# linearInjector_main.net
KiCad netlist of a schematic drawn in Altium Designer
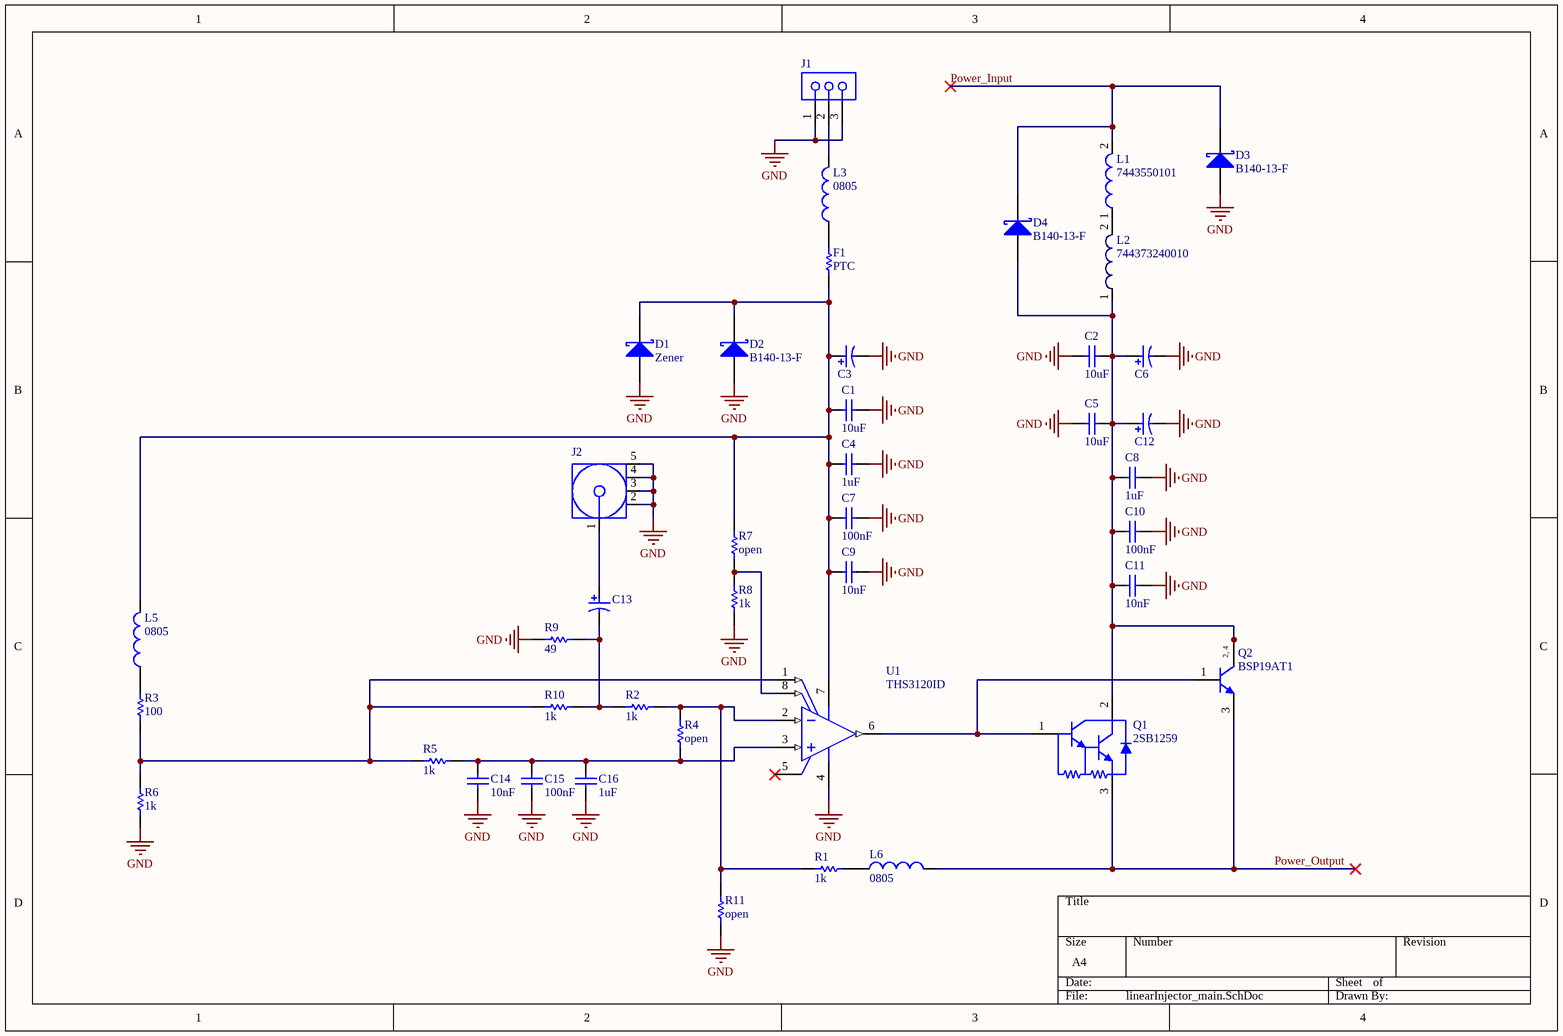
[diagram p0: linearInjector_main.SchDoc]

(export (version "E")
  (design (tool "Eeschema 10.0.6"))
  (components
    (comp (ref "C1")
      (value "10uF")
      (footprint "CAPC1206(3216)130_M")
      (fields (field (name "TOLERANCE") "-20% to +80%"))
      (libsource (lib "Altium Content Vault") (part "CAP"))
    )
    (comp (ref "C2")
      (value "10uF")
      (footprint "CAPC1206(3216)130_L")
      (fields (field (name "TOLERANCE") "-20% to +80%"))
      (libsource (lib "Altium Content Vault") (part "CAP"))
    )
    (comp (ref "C3")
      (value "alum")
      (footprint "PNSC-NF-A_V")
      (description "5mm lead pitch")
      (fields (field (name "VOLTAGE") "5.5Vdc") (field (name "TOLERANCE") "-20→+80%"))
      (libsource (lib "Altium Content Vault") (part "CAP-P-2"))
    )
    (comp (ref "C4")
      (value "1uF")
      (footprint "CAPC0805(2012)75_M")
      (fields (field (name "TOLERANCE") "-20% to +80%"))
      (libsource (lib "Altium Content Vault") (part "CAP"))
    )
    (comp (ref "C5")
      (value "10uF")
      (footprint "CAPC1206(3216)130_L")
      (fields (field (name "TOLERANCE") "-20% to +80%"))
      (libsource (lib "Altium Content Vault") (part "CAP"))
    )
    (comp (ref "C6")
      (value "alum")
      (footprint "PNSC-NF-A_V")
      (description "5mm lead pitch")
      (fields (field (name "VOLTAGE") "5.5Vdc") (field (name "TOLERANCE") "-20→+80%"))
      (libsource (lib "Altium Content Vault") (part "CAP-P-2"))
    )
    (comp (ref "C7")
      (value "100nF")
      (footprint "CAPC0805(2012)75_M")
      (fields (field (name "TOLERANCE") "-20% to +80%"))
      (libsource (lib "Altium Content Vault") (part "CAP"))
    )
    (comp (ref "C8")
      (value "1uF")
      (footprint "CAPC0805(2012)75_M")
      (fields (field (name "TOLERANCE") "-20% to +80%"))
      (libsource (lib "Altium Content Vault") (part "CAP"))
    )
    (comp (ref "C9")
      (value "10nF")
      (footprint "CAPC0805(2012)75_M")
      (fields (field (name "TOLERANCE") "-20% to +80%"))
      (libsource (lib "Altium Content Vault") (part "CAP"))
    )
    (comp (ref "C10")
      (value "100nF")
      (footprint "CAPC0805(2012)75_M")
      (fields (field (name "TOLERANCE") "-20% to +80%"))
      (libsource (lib "Altium Content Vault") (part "CAP"))
    )
    (comp (ref "C11")
      (value "10nF")
      (footprint "CAPC0805(2012)75_M")
      (fields (field (name "TOLERANCE") "-20% to +80%"))
      (libsource (lib "Altium Content Vault") (part "CAP"))
    )
    (comp (ref "C12")
      (value "alum")
      (footprint "PNSC-NF-A_V")
      (description "5mm lead pitch")
      (fields (field (name "VOLTAGE") "5.5Vdc") (field (name "TOLERANCE") "-20→+80%"))
      (libsource (lib "Altium Content Vault") (part "CAP-P-2"))
    )
    (comp (ref "C13")
      (value "alum")
      (footprint "PNSC-NF-A_V")
      (description "5mm lead pitch")
      (fields (field (name "VOLTAGE") "5.5Vdc") (field (name "TOLERANCE") "-20→+80%"))
      (libsource (lib "Altium Content Vault") (part "CAP-P-2"))
    )
    (comp (ref "C14")
      (value "10nF")
      (footprint "CAPC0805(2012)75_M")
      (fields (field (name "TOLERANCE") "-20% to +80%"))
      (libsource (lib "Altium Content Vault") (part "CAP"))
    )
    (comp (ref "C15")
      (value "100nF")
      (footprint "CAPC0805(2012)75_M")
      (fields (field (name "TOLERANCE") "-20% to +80%"))
      (libsource (lib "Altium Content Vault") (part "CAP"))
    )
    (comp (ref "C16")
      (value "1uF")
      (footprint "CAPC0805(2012)75_M")
      (fields (field (name "TOLERANCE") "-20% to +80%"))
      (libsource (lib "Altium Content Vault") (part "CAP"))
    )
    (comp (ref "D1")
      (value "Zener")
      (footprint "DIOD-B1X0-2_V")
      (description "option")
      (fields (field (name "MANUFACTURER") "DiodesIncorporated"))
      (libsource (lib "Altium Content Vault") (part "DSKY-KA-2"))
    )
    (comp (ref "D2")
      (value "B140-13-F")
      (footprint "DIOD-B1X0-2_V")
      (description "Surface Mount Schottky Barrier Rectifier, 1 A, -65 to 150 degC, 2-Pin SMA, RoHS, Tape and Reel")
      (fields (field (name "MANUFACTURER") "DiodesIncorporated"))
      (libsource (lib "Altium Content Vault") (part "DSKY-KA-2"))
    )
    (comp (ref "D3")
      (value "B140-13-F")
      (footprint "DIOD-B1X0-2_V")
      (description "Surface Mount Schottky Barrier Rectifier, 1 A, -65 to 150 degC, 2-Pin SMA, RoHS, Tape and Reel")
      (fields (field (name "MANUFACTURER") "DiodesIncorporated"))
      (libsource (lib "Altium Content Vault") (part "DSKY-KA-2"))
    )
    (comp (ref "D4")
      (value "B140-13-F")
      (footprint "DIOD-B1X0-2_V")
      (description "Surface Mount Schottky Barrier Rectifier, 1 A, -65 to 150 degC, 2-Pin SMA, RoHS, Tape and Reel")
      (fields (field (name "MANUFACTURER") "DiodesIncorporated"))
      (libsource (lib "Altium Content Vault") (part "DSKY-KA-2"))
    )
    (comp (ref "F1")
      (value "PTC")
      (footprint "RESC1206(3216)_M")
      (description "Fuse")
      (fields (field (name "TOLERANCE") "1 %") (field (name "POWER") "0.25 W"))
      (libsource (lib "Altium Content Vault") (part "RES"))
    )
    (comp (ref "J1")
      (value "BCS-103-L-S-TE")
      (footprint "SMTC-BCS-103-X-S-TE")
      (description "Tiger Claw(TM) Pass-Through Socket, Vertical, -55 to 125 degC, 2.54 mm Pitch, 3-Pin, Female, RoHS")
      (fields (field (name "MANUFACTURER") "Samtec"))
      (libsource (lib "Altium Content Vault") (part "SMTC-BCS-103-X-S-TE"))
    )
    (comp (ref "J2")
      (value "LTI-SASF54GT")
      (footprint "LHT-LTI-SASF54GT_V")
      (description "SMA Connector, Pitch 2.54 mm, 1 Position, Height 9.5 mm, Tail Length 4 mm, RoHS")
      (fields (field (name "MANUFACTURER") "Lighthorse Technologies Inc."))
      (libsource (lib "Altium Content Vault") (part "CN-S-F-RF5"))
    )
    (comp (ref "L1")
      (value "7443550101")
      (footprint "WE-HCI-1350")
      (description "SMD Flat Wire High Current Inductor WE-HCI, L=10.0 µH")
      (libsource (lib "Altium Content Vault") (part "PAS-IND-INDUCTOR-2"))
    )
    (comp (ref "L2")
      (value "744373240010")
      (footprint "WE-LHMI 4020")
      (description "SMD Power Inductor WE-LHMI, L=0.10 µH")
      (fields (field (name "MANUFACTURER") "Wuerth Elektronik"))
      (libsource (lib "Altium Content Vault") (part "WE-IND-INDUCTOR-2"))
    )
    (comp (ref "L3")
      (value "0805")
      (footprint "INDC2013X105X50ML20T30")
      (fields (field (name "TOLERANCE") "30%"))
      (libsource (lib "Altium Content Vault") (part "IND-2"))
    )
    (comp (ref "L5")
      (value "0805")
      (footprint "INDC2013X105X50ML20T30")
      (fields (field (name "TOLERANCE") "30%"))
      (libsource (lib "Altium Content Vault") (part "IND-2"))
    )
    (comp (ref "L6")
      (value "0805")
      (footprint "INDC2013X105X50ML20T30")
      (fields (field (name "TOLERANCE") "30%"))
      (libsource (lib "Altium Content Vault") (part "IND-2"))
    )
    (comp (ref "Q1")
      (value "2SB1259")
      (footprint "ONSC-TO-220-3-221A-09")
      (fields (field (name "PARTNUMBER") "MJE5740G") (field (name "MANUFACTURER") "On Semiconductor"))
      (libsource (lib "Altium Content Vault") (part "ONSC-DT-NPN-B1C2E3-3_A"))
    )
    (comp (ref "Q2")
      (value "BSP19AT1")
      (footprint "ONSC-SOT-223-4-318E-04_V")
      (description "NPN Silicon Expitaxial Transistor, 4-Pin SOT-223, Tape and Reel")
      (fields (field (name "MANUFACTURER") "On Semiconductor"))
      (libsource (lib "Altium Content Vault") (part "ONSC-NPN-B1C2E3C4-4"))
    )
    (comp (ref "R1")
      (value "1k")
      (footprint "RESC0805(2012)_M")
      (description "1k 1%")
      (fields (field (name "TOLERANCE") "1 %") (field (name "POWER") "0.125 W"))
      (libsource (lib "Altium Content Vault") (part "RES"))
    )
    (comp (ref "R2")
      (value "1k")
      (footprint "RESC0805(2012)_M")
      (description "1k 1%")
      (fields (field (name "TOLERANCE") "1 %") (field (name "POWER") "0.125 W"))
      (libsource (lib "Altium Content Vault") (part "RES"))
    )
    (comp (ref "R3")
      (value "100")
      (footprint "RESC0805(2012)_M")
      (description "1k 1%")
      (fields (field (name "TOLERANCE") "1 %") (field (name "POWER") "0.125 W"))
      (libsource (lib "Altium Content Vault") (part "RES"))
    )
    (comp (ref "R4")
      (value "open")
      (footprint "RESC0805(2012)_M")
      (fields (field (name "TOLERANCE") "1 %") (field (name "POWER") "0.125 W"))
      (libsource (lib "Altium Content Vault") (part "RES"))
    )
    (comp (ref "R5")
      (value "1k")
      (footprint "RESC0805(2012)_M")
      (description "1k 1%")
      (fields (field (name "TOLERANCE") "1 %") (field (name "POWER") "0.125 W"))
      (libsource (lib "Altium Content Vault") (part "RES"))
    )
    (comp (ref "R6")
      (value "1k")
      (footprint "RESC0805(2012)_M")
      (description "1k 1%")
      (fields (field (name "TOLERANCE") "1 %") (field (name "POWER") "0.125 W"))
      (libsource (lib "Altium Content Vault") (part "RES"))
    )
    (comp (ref "R7")
      (value "open")
      (footprint "RESC0805(2012)_M")
      (description "1k 1%")
      (fields (field (name "TOLERANCE") "1 %") (field (name "POWER") "0.125 W"))
      (libsource (lib "Altium Content Vault") (part "RES"))
    )
    (comp (ref "R8")
      (value "1k")
      (footprint "RESC0805(2012)_M")
      (description "1k 1%")
      (fields (field (name "TOLERANCE") "1 %") (field (name "POWER") "0.125 W"))
      (libsource (lib "Altium Content Vault") (part "RES"))
    )
    (comp (ref "R9")
      (value "49")
      (footprint "RESC0805(2012)_M")
      (description "1k 1%")
      (fields (field (name "TOLERANCE") "1 %") (field (name "POWER") "0.125 W"))
      (libsource (lib "Altium Content Vault") (part "RES"))
    )
    (comp (ref "R10")
      (value "1k")
      (footprint "RESC0805(2012)_M")
      (description "1k 1%")
      (fields (field (name "TOLERANCE") "1 %") (field (name "POWER") "0.125 W"))
      (libsource (lib "Altium Content Vault") (part "RES"))
    )
    (comp (ref "R11")
      (value "open")
      (footprint "RESC0805(2012)_M")
      (description "1k 1%")
      (fields (field (name "TOLERANCE") "1 %") (field (name "POWER") "0.125 W"))
      (libsource (lib "Altium Content Vault") (part "RES"))
    )
    (comp (ref "U1")
      (value "THS3120ID")
      (footprint "D0008A_L")
      (fields (field (name "MANUFACTURER") "Texas Instruments"))
      (libsource (lib "Altium Content Vault") (part "TI-THS3110_3120D8"))
    )
  )
  (nets
    (net (code "1") (name "/Power_Input") (class "Default")
      (node (ref "D3") (pin "1") (pinfunction "K_1") (pintype "passive"))
      (node (ref "D4") (pin "1") (pinfunction "K_1") (pintype "passive"))
      (node (ref "L1") (pin "2") (pinfunction "2_2") (pintype "passive"))
    )
    (net (code "2") (name "/Power_Output") (class "Default")
      (node (ref "L6") (pin "2") (pinfunction "2_2") (pintype "passive"))
      (node (ref "Q1") (pin "3") (pinfunction "E_3") (pintype "passive"))
      (node (ref "Q2") (pin "3") (pinfunction "E_3") (pintype "passive"))
    )
    (net (code "3") (name "GND") (class "Default")
      (node (ref "C1") (pin "2") (pinfunction "2_2") (pintype "passive"))
      (node (ref "C10") (pin "1") (pinfunction "1_1") (pintype "passive"))
      (node (ref "C11") (pin "1") (pinfunction "1_1") (pintype "passive"))
      (node (ref "C12") (pin "2") (pinfunction "2_2") (pintype "passive"))
      (node (ref "C14") (pin "1") (pinfunction "1_1") (pintype "passive"))
      (node (ref "C15") (pin "1") (pinfunction "1_1") (pintype "passive"))
      (node (ref "C16") (pin "1") (pinfunction "1_1") (pintype "passive"))
      (node (ref "C2") (pin "2") (pinfunction "2_2") (pintype "passive"))
      (node (ref "C3") (pin "2") (pinfunction "2_2") (pintype "passive"))
      (node (ref "C4") (pin "1") (pinfunction "1_1") (pintype "passive"))
      (node (ref "C5") (pin "2") (pinfunction "2_2") (pintype "passive"))
      (node (ref "C6") (pin "2") (pinfunction "2_2") (pintype "passive"))
      (node (ref "C7") (pin "1") (pinfunction "1_1") (pintype "passive"))
      (node (ref "C8") (pin "1") (pinfunction "1_1") (pintype "passive"))
      (node (ref "C9") (pin "1") (pinfunction "1_1") (pintype "passive"))
      (node (ref "D1") (pin "2") (pinfunction "A_2") (pintype "passive"))
      (node (ref "D2") (pin "2") (pinfunction "A_2") (pintype "passive"))
      (node (ref "D3") (pin "2") (pinfunction "A_2") (pintype "passive"))
      (node (ref "J1") (pin "1") (pinfunction "1_1") (pintype "passive"))
      (node (ref "J1") (pin "3") (pinfunction "3_3") (pintype "passive"))
      (node (ref "J2") (pin "2") (pinfunction "2_2") (pintype "passive"))
      (node (ref "J2") (pin "3") (pinfunction "3_3") (pintype "passive"))
      (node (ref "J2") (pin "4") (pinfunction "4_4") (pintype "passive"))
      (node (ref "J2") (pin "5") (pinfunction "5_5") (pintype "passive"))
      (node (ref "R11") (pin "1") (pinfunction "1_1") (pintype "passive"))
      (node (ref "R6") (pin "1") (pinfunction "1_1") (pintype "passive"))
      (node (ref "R8") (pin "1") (pinfunction "1_1") (pintype "passive"))
      (node (ref "R9") (pin "1") (pinfunction "1_1") (pintype "passive"))
      (node (ref "U1") (pin "4") (pinfunction "VS-_4") (pintype "power_in"))
    )
    (net (code "4") (name "Net-(C13-Pad1)") (class "Default")
      (node (ref "C13") (pin "1") (pinfunction "1_1") (pintype "passive"))
      (node (ref "J2") (pin "1") (pinfunction "1_1") (pintype "passive"))
    )
    (net (code "5") (name "Net-(C13-Pad2)") (class "Default")
      (node (ref "C13") (pin "2") (pinfunction "2_2") (pintype "passive"))
      (node (ref "R10") (pin "2") (pinfunction "2_2") (pintype "passive"))
      (node (ref "R2") (pin "1") (pinfunction "1_1") (pintype "passive"))
      (node (ref "R9") (pin "2") (pinfunction "2_2") (pintype "passive"))
    )
    (net (code "6") (name "Net-(D1-K)") (class "Default")
      (node (ref "C1") (pin "1") (pinfunction "1_1") (pintype "passive"))
      (node (ref "C3") (pin "1") (pinfunction "1_1") (pintype "passive"))
      (node (ref "C4") (pin "2") (pinfunction "2_2") (pintype "passive"))
      (node (ref "C7") (pin "2") (pinfunction "2_2") (pintype "passive"))
      (node (ref "C9") (pin "2") (pinfunction "2_2") (pintype "passive"))
      (node (ref "D1") (pin "1") (pinfunction "K_1") (pintype "passive"))
      (node (ref "D2") (pin "1") (pinfunction "K_1") (pintype "passive"))
      (node (ref "F1") (pin "1") (pinfunction "1_1") (pintype "passive"))
      (node (ref "L5") (pin "2") (pinfunction "2_2") (pintype "passive"))
      (node (ref "R7") (pin "2") (pinfunction "2_2") (pintype "passive"))
      (node (ref "U1") (pin "7") (pinfunction "VS+_7") (pintype "power_in"))
    )
    (net (code "7") (name "Net-(D4-A)") (class "Default")
      (node (ref "C10") (pin "2") (pinfunction "2_2") (pintype "passive"))
      (node (ref "C11") (pin "2") (pinfunction "2_2") (pintype "passive"))
      (node (ref "C12") (pin "1") (pinfunction "1_1") (pintype "passive"))
      (node (ref "C2") (pin "1") (pinfunction "1_1") (pintype "passive"))
      (node (ref "C5") (pin "1") (pinfunction "1_1") (pintype "passive"))
      (node (ref "C6") (pin "1") (pinfunction "1_1") (pintype "passive"))
      (node (ref "C8") (pin "2") (pinfunction "2_2") (pintype "passive"))
      (node (ref "D4") (pin "2") (pinfunction "A_2") (pintype "passive"))
      (node (ref "L2") (pin "1") (pinfunction "1_1") (pintype "passive"))
      (node (ref "Q1") (pin "2") (pinfunction "C_2") (pintype "passive"))
      (node (ref "Q2") (pin "2") (pinfunction "C_2") (pintype "passive"))
      (node (ref "Q2") (pin "4") (pinfunction "C_4") (pintype "passive"))
    )
    (net (code "8") (name "Net-(F1-Pad2)") (class "Default")
      (node (ref "F1") (pin "2") (pinfunction "2_2") (pintype "passive"))
      (node (ref "L3") (pin "1") (pinfunction "1_1") (pintype "passive"))
    )
    (net (code "9") (name "Net-(J1-Pad2)") (class "Default")
      (node (ref "J1") (pin "2") (pinfunction "2_2") (pintype "passive"))
      (node (ref "L3") (pin "2") (pinfunction "2_2") (pintype "passive"))
    )
    (net (code "10") (name "Net-(L1-Pad1)") (class "Default")
      (node (ref "L1") (pin "1") (pinfunction "1_1") (pintype "passive"))
      (node (ref "L2") (pin "2") (pinfunction "2_2") (pintype "passive"))
    )
    (net (code "11") (name "Net-(L5-Pad1)") (class "Default")
      (node (ref "L5") (pin "1") (pinfunction "1_1") (pintype "passive"))
      (node (ref "R3") (pin "2") (pinfunction "2_2") (pintype "passive"))
    )
    (net (code "12") (name "Net-(L6-Pad1)") (class "Default")
      (node (ref "L6") (pin "1") (pinfunction "1_1") (pintype "passive"))
      (node (ref "R1") (pin "2") (pinfunction "2_2") (pintype "passive"))
    )
    (net (code "13") (name "Net-(Q1-B)") (class "Default")
      (node (ref "Q1") (pin "1") (pinfunction "B_1") (pintype "passive"))
      (node (ref "Q2") (pin "1") (pinfunction "B_1") (pintype "passive"))
      (node (ref "U1") (pin "6") (pinfunction "VOUT_6") (pintype "output"))
    )
    (net (code "14") (name "Net-(U1-PD)") (class "Default")
      (node (ref "R7") (pin "1") (pinfunction "1_1") (pintype "passive"))
      (node (ref "R8") (pin "2") (pinfunction "2_2") (pintype "passive"))
      (node (ref "U1") (pin "8") (pinfunction "PD_8") (pintype "input"))
    )
    (net (code "15") (name "Net-(U1-REF)") (class "Default")
      (node (ref "R10") (pin "1") (pinfunction "1_1") (pintype "passive"))
      (node (ref "R3") (pin "1") (pinfunction "1_1") (pintype "passive"))
      (node (ref "R5") (pin "1") (pinfunction "1_1") (pintype "passive"))
      (node (ref "R6") (pin "2") (pinfunction "2_2") (pintype "passive"))
      (node (ref "U1") (pin "1") (pinfunction "REF_1") (pintype "input"))
    )
    (net (code "16") (name "Net-(U1-VIN+)") (class "Default")
      (node (ref "C14") (pin "2") (pinfunction "2_2") (pintype "passive"))
      (node (ref "C15") (pin "2") (pinfunction "2_2") (pintype "passive"))
      (node (ref "C16") (pin "2") (pinfunction "2_2") (pintype "passive"))
      (node (ref "R4") (pin "1") (pinfunction "1_1") (pintype "passive"))
      (node (ref "R5") (pin "2") (pinfunction "2_2") (pintype "passive"))
      (node (ref "U1") (pin "3") (pinfunction "VIN+_3") (pintype "input"))
    )
    (net (code "17") (name "Net-(U1-VIN-)") (class "Default")
      (node (ref "R1") (pin "1") (pinfunction "1_1") (pintype "passive"))
      (node (ref "R11") (pin "2") (pinfunction "2_2") (pintype "passive"))
      (node (ref "R2") (pin "2") (pinfunction "2_2") (pintype "passive"))
      (node (ref "R4") (pin "2") (pinfunction "2_2") (pintype "passive"))
      (node (ref "U1") (pin "2") (pinfunction "VIN-_2") (pintype "input"))
    )
    (net (code "18") (name "unconnected-(U1-NC-Pad5)") (class "Default")
      (node (ref "U1") (pin "5") (pinfunction "NC_5") (pintype "passive+no_connect"))
    )
  )
)
